# bib.net
KiCad netlist of a schematic drawn in EAGLE
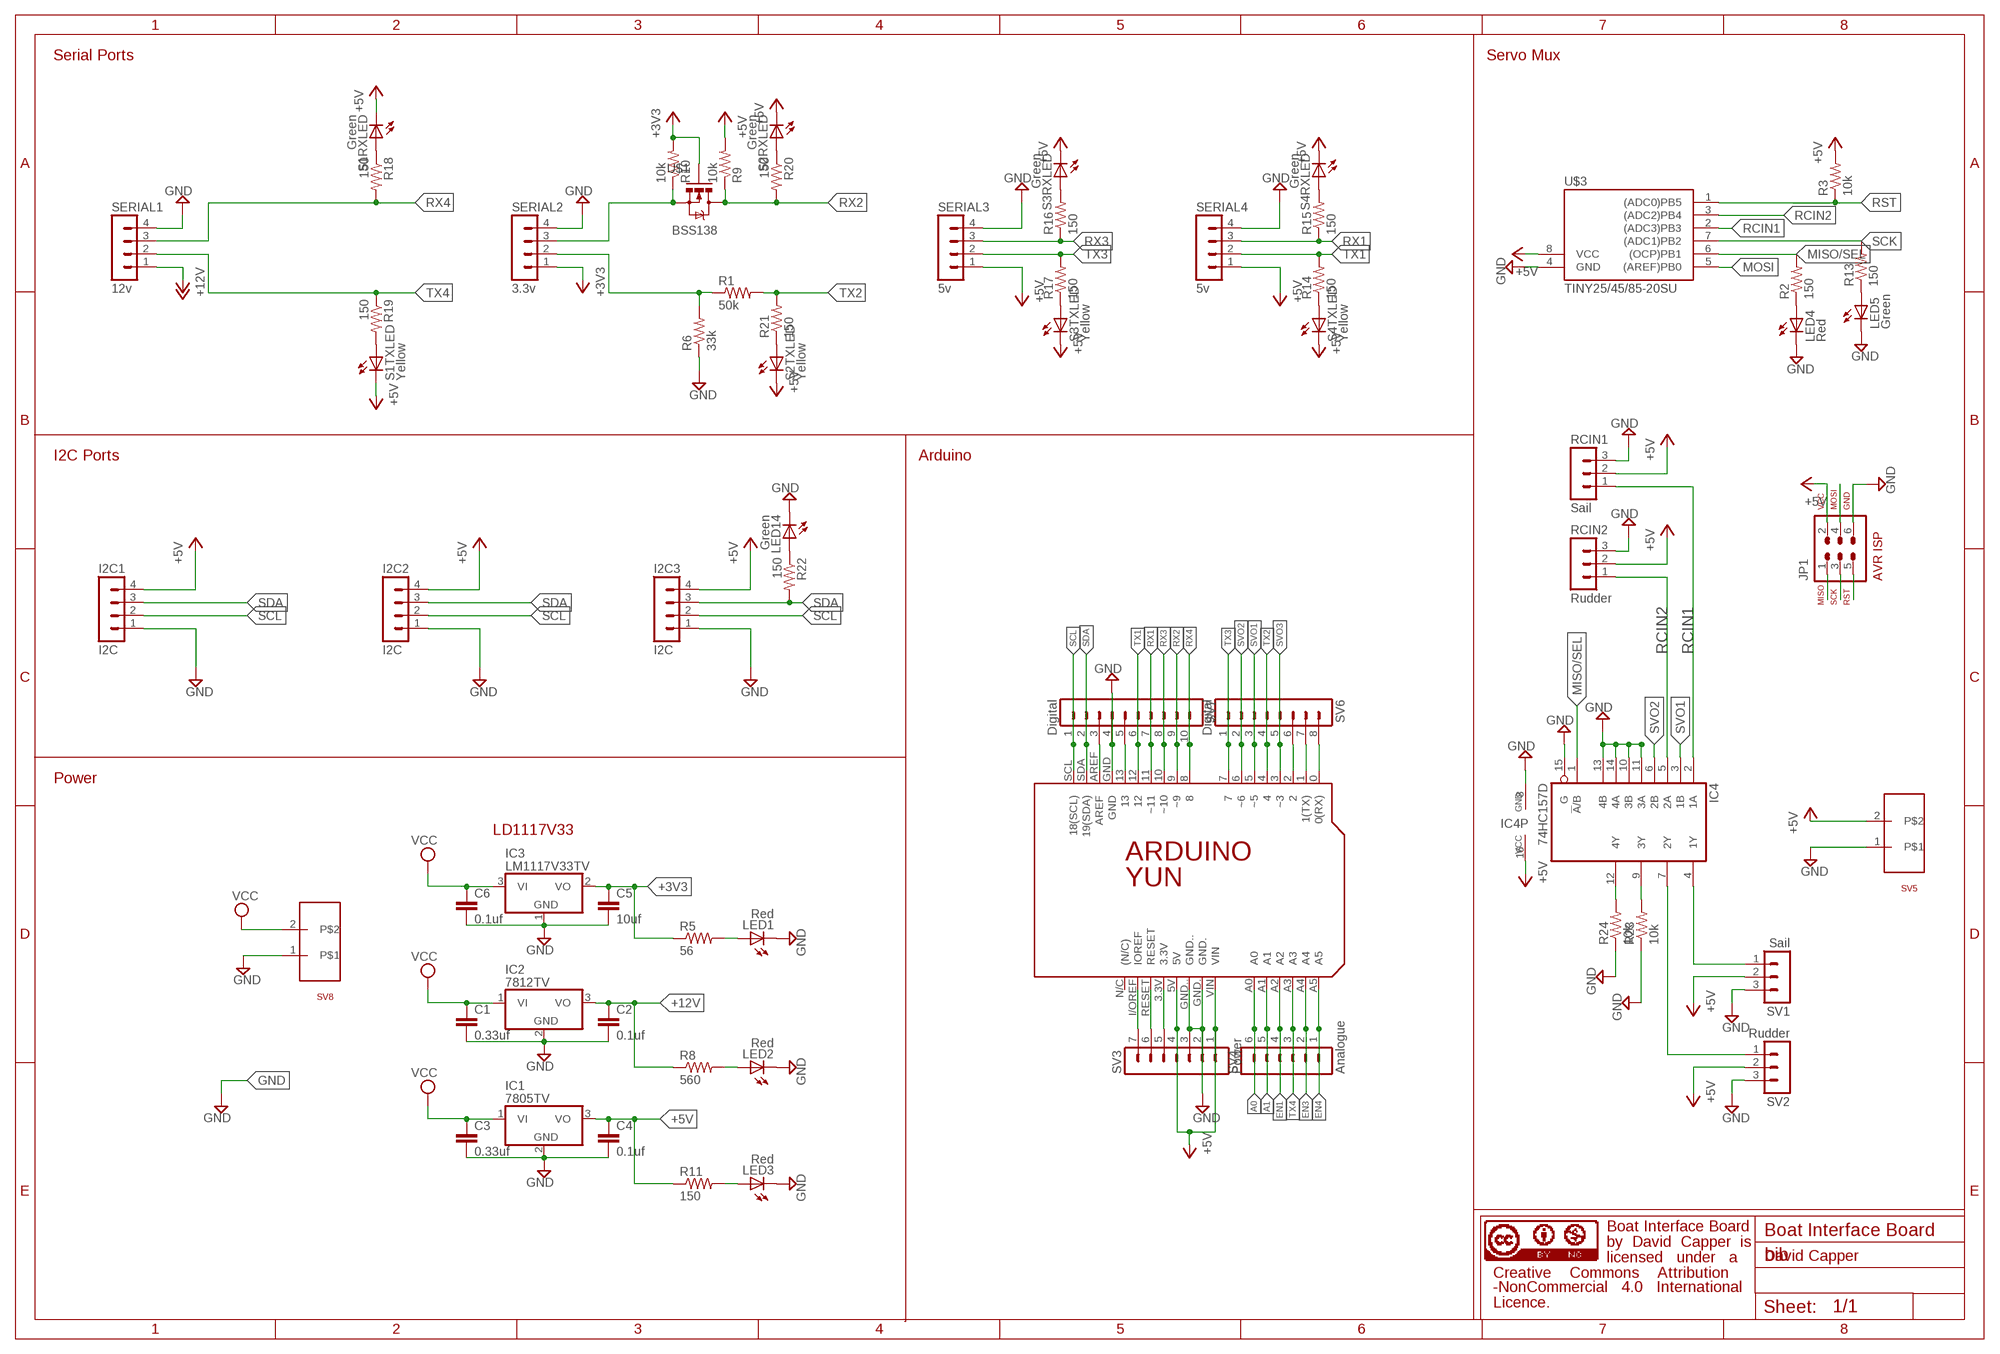
[diagram p0: schematic, sheet 1]

(export (version "E")
  (design (tool "Eeschema 10.0.6"))
  (components
    (comp (ref "C1")
      (value "0.33uf")
      (footprint "eagle-import:C0805K")
      (fields (field (name "MF") "AVX") (field (name "MPN") "08053C334KAT2A"))
      (libsource (lib "eagle-import") (part "C-EUC0805K"))
    )
    (comp (ref "C2")
      (value "0.1uf")
      (footprint "eagle-import:C0805K")
      (fields (field (name "MF") "AVX") (field (name "MPN") "08051C104JAT2A"))
      (libsource (lib "eagle-import") (part "C-EUC0805K"))
    )
    (comp (ref "C3")
      (value "0.33uf")
      (footprint "eagle-import:C0805K")
      (fields (field (name "MF") "AVX") (field (name "MPN") "08053C334KAT2A"))
      (libsource (lib "eagle-import") (part "C-EUC0805K"))
    )
    (comp (ref "C4")
      (value "0.1uf")
      (footprint "eagle-import:C0805K")
      (fields (field (name "MF") "AVX") (field (name "MPN") "08051C104JAT2A"))
      (libsource (lib "eagle-import") (part "C-EUC0805K"))
    )
    (comp (ref "C5")
      (value "10uf")
      (footprint "eagle-import:C0805K")
      (fields (field (name "MF") "YAGEO (PHYCOMP)") (field (name "MPN") "CC0805KRX7R8BB333"))
      (libsource (lib "eagle-import") (part "C-EUC0805K"))
    )
    (comp (ref "C6")
      (value "0.1uf")
      (footprint "eagle-import:C0805K")
      (fields (field (name "MF") "AVX") (field (name "MPN") "08051C104JAT2A"))
      (libsource (lib "eagle-import") (part "C-EUC0805K"))
    )
    (comp (ref "I2C1")
      (value "I2C")
      (footprint "eagle-import:MA04-1")
      (libsource (lib "eagle-import") (part "MA04-1"))
    )
    (comp (ref "I2C2")
      (value "I2C")
      (footprint "eagle-import:MA04-1")
      (libsource (lib "eagle-import") (part "MA04-1"))
    )
    (comp (ref "I2C3")
      (value "I2C")
      (footprint "eagle-import:MA04-1")
      (libsource (lib "eagle-import") (part "MA04-1"))
    )
    (comp (ref "IC1")
      (value "7805TV")
      (footprint "eagle-import:TO220V")
      (fields (field (name "MF") "STMICROELECTRONICS") (field (name "MPN") "L7805ACV"))
      (libsource (lib "eagle-import") (part "78TV05"))
    )
    (comp (ref "IC2")
      (value "7812TV")
      (footprint "eagle-import:TO220V")
      (fields (field (name "MF") "STMICROELECTRONICS") (field (name "MPN") "L7812ACV"))
      (libsource (lib "eagle-import") (part "78TV12"))
    )
    (comp (ref "IC3")
      (value "LM1117V33TV")
      (footprint "eagle-import:TO220V")
      (fields (field (name "MF") "STMICROELECTRONICS") (field (name "MPN") "LD1117V33"))
      (libsource (lib "eagle-import") (part "LM1117V33TV"))
    )
    (comp (ref "IC4")
      (value "74HC157D")
      (footprint "eagle-import:SO16")
      (fields
        (field (name "MF") "TEXAS INSTRUMENTS")
        (field (name "MPN") "SN74HC157D")
        (field (name "OC_FARNELL") "9591150")
      )
      (libsource (lib "eagle-import") (part "74157DHC"))
    )
    (comp (ref "JP1")
      (value "AVR-ISP-6VERT")
      (footprint "eagle-import:AVR-ISP-6")
      (libsource (lib "eagle-import") (part "AVR-ISP-6VERT"))
    )
    (comp (ref "LED1")
      (value "Red")
      (footprint "eagle-import:SML1206")
      (fields (field (name "MF") "KINGBRIGHT") (field (name "MPN") "KPT-3216SRC-J4"))
      (libsource (lib "eagle-import") (part "LEDSML1206"))
    )
    (comp (ref "LED2")
      (value "Red")
      (footprint "eagle-import:SML1206")
      (fields (field (name "MF") "KINGBRIGHT") (field (name "MPN") "KPT-3216SRC-J4"))
      (libsource (lib "eagle-import") (part "LEDSML1206"))
    )
    (comp (ref "LED3")
      (value "Red")
      (footprint "eagle-import:SML1206")
      (fields (field (name "MF") "KINGBRIGHT") (field (name "MPN") "KPT-3216SRC-J4"))
      (libsource (lib "eagle-import") (part "LEDSML1206"))
    )
    (comp (ref "LED4")
      (value "Red")
      (footprint "eagle-import:SML1206")
      (fields (field (name "MF") "KINGBRIGHT") (field (name "MPN") "KPT-3216SGC"))
      (libsource (lib "eagle-import") (part "LEDSML1206"))
    )
    (comp (ref "LED5")
      (value "Green")
      (footprint "eagle-import:SML1206")
      (fields (field (name "MF") "KINGBRIGHT") (field (name "MPN") "KPT-3216SGC"))
      (libsource (lib "eagle-import") (part "LEDSML1206"))
    )
    (comp (ref "LED14")
      (value "Green")
      (footprint "eagle-import:SML1206")
      (fields (field (name "MF") "KINGBRIGHT") (field (name "MPN") "KPT-3216SGC"))
      (libsource (lib "eagle-import") (part "LEDSML1206"))
    )
    (comp (ref "PCB2")
      (value "ARDUINO_YUNARDUINO_YUN")
      (footprint "eagle-import:ARDUINO_YUN")
      (libsource (lib "eagle-import") (part "ARDUINO_YUNARDUINO_YUN"))
    )
    (comp (ref "R1")
      (value "50k")
      (footprint "eagle-import:M0805")
      (fields (field (name "MF") "VISHAY DRALORIC") (field (name "MPN") "CRCW080533K0FKEA"))
      (libsource (lib "eagle-import") (part "R-US_M0805"))
    )
    (comp (ref "R2")
      (value "150")
      (footprint "eagle-import:R0805")
      (fields (field (name "MF") "VISHAY DRALORIC") (field (name "MPN") "CRCW0805150RFKEAHP"))
      (libsource (lib "eagle-import") (part "R-US_R0805"))
    )
    (comp (ref "R3")
      (value "10k")
      (footprint "eagle-import:R0805")
      (fields (field (name "MF") "VISHAY DRALORIC") (field (name "MPN") "CRCW0805150RFKEAHP"))
      (libsource (lib "eagle-import") (part "R-US_R0805"))
    )
    (comp (ref "R5")
      (value "56")
      (footprint "eagle-import:R0805")
      (fields (field (name "MF") "VISHAY DRALORIC") (field (name "MPN") "CRCW080556R0FKEAHP"))
      (libsource (lib "eagle-import") (part "R-US_R0805"))
    )
    (comp (ref "R6")
      (value "33k")
      (footprint "eagle-import:M0805")
      (fields (field (name "MF") "VISHAY DRALORIC") (field (name "MPN") "CRCW080549K9FKEA"))
      (libsource (lib "eagle-import") (part "R-US_M0805"))
    )
    (comp (ref "R8")
      (value "560")
      (footprint "eagle-import:R0805")
      (fields (field (name "MF") "VISHAY DRALORIC") (field (name "MPN") "CRCW0805560RFKEAHP"))
      (libsource (lib "eagle-import") (part "R-US_R0805"))
    )
    (comp (ref "R9")
      (value "10k")
      (footprint "eagle-import:M0805")
      (fields (field (name "MF") "VISHAY DRALORIC") (field (name "MPN") "CRCW080510K0FKEA"))
      (libsource (lib "eagle-import") (part "R-US_M0805"))
    )
    (comp (ref "R10")
      (value "10k")
      (footprint "eagle-import:M0805")
      (fields (field (name "MF") "VISHAY DRALORIC") (field (name "MPN") "CRCW080510K0FKEA"))
      (libsource (lib "eagle-import") (part "R-US_M0805"))
    )
    (comp (ref "R11")
      (value "150")
      (footprint "eagle-import:R0805")
      (fields (field (name "MF") "VISHAY DRALORIC") (field (name "MPN") "CRCW0805150RFKEAHP"))
      (libsource (lib "eagle-import") (part "R-US_R0805"))
    )
    (comp (ref "R13")
      (value "150")
      (footprint "eagle-import:R0805")
      (fields (field (name "MF") "VISHAY DRALORIC") (field (name "MPN") "CRCW0805150RFKEAHP"))
      (libsource (lib "eagle-import") (part "R-US_R0805"))
    )
    (comp (ref "R14")
      (value "150")
      (footprint "eagle-import:R0805")
      (fields (field (name "MF") "VISHAY DRALORIC") (field (name "MPN") "CRCW0805150RFKEAHP"))
      (libsource (lib "eagle-import") (part "R-US_R0805"))
    )
    (comp (ref "R15")
      (value "150")
      (footprint "eagle-import:R0805")
      (fields (field (name "MF") "VISHAY DRALORIC") (field (name "MPN") "CRCW0805150RFKEAHP"))
      (libsource (lib "eagle-import") (part "R-US_R0805"))
    )
    (comp (ref "R16")
      (value "150")
      (footprint "eagle-import:R0805")
      (fields (field (name "MF") "VISHAY DRALORIC") (field (name "MPN") "CRCW0805150RFKEAHP"))
      (libsource (lib "eagle-import") (part "R-US_R0805"))
    )
    (comp (ref "R17")
      (value "150")
      (footprint "eagle-import:R0805")
      (fields (field (name "MF") "VISHAY DRALORIC") (field (name "MPN") "CRCW0805150RFKEAHP"))
      (libsource (lib "eagle-import") (part "R-US_R0805"))
    )
    (comp (ref "R18")
      (value "150")
      (footprint "eagle-import:R0805")
      (fields (field (name "MF") "VISHAY DRALORIC") (field (name "MPN") "CRCW0805150RFKEAHP"))
      (libsource (lib "eagle-import") (part "R-US_R0805"))
    )
    (comp (ref "R19")
      (value "150")
      (footprint "eagle-import:R0805")
      (fields (field (name "MF") "VISHAY DRALORIC") (field (name "MPN") "CRCW0805150RFKEAHP"))
      (libsource (lib "eagle-import") (part "R-US_R0805"))
    )
    (comp (ref "R20")
      (value "150")
      (footprint "eagle-import:R0805")
      (fields (field (name "MF") "VISHAY DRALORIC") (field (name "MPN") "CRCW0805150RFKEAHP"))
      (libsource (lib "eagle-import") (part "R-US_R0805"))
    )
    (comp (ref "R21")
      (value "150")
      (footprint "eagle-import:R0805")
      (fields (field (name "MF") "VISHAY DRALORIC") (field (name "MPN") "CRCW0805150RFKEAHP"))
      (libsource (lib "eagle-import") (part "R-US_R0805"))
    )
    (comp (ref "R22")
      (value "150")
      (footprint "eagle-import:R0805")
      (fields (field (name "MF") "VISHAY DRALORIC") (field (name "MPN") "CRCW0805150RFKEAHP"))
      (libsource (lib "eagle-import") (part "R-US_R0805"))
    )
    (comp (ref "R23")
      (value "10k")
      (footprint "eagle-import:R0805")
      (fields (field (name "MF") "VISHAY DRALORIC") (field (name "MPN") "CRCW080510K0FKEA"))
      (libsource (lib "eagle-import") (part "R-US_R0805"))
    )
    (comp (ref "R24")
      (value "10k")
      (footprint "eagle-import:R0805")
      (fields (field (name "MF") "VISHAY DRALORIC") (field (name "MPN") "CRCW080510K0FKEA"))
      (libsource (lib "eagle-import") (part "R-US_R0805"))
    )
    (comp (ref "RCIN1")
      (value "Sail")
      (footprint "eagle-import:MA03-1")
      (libsource (lib "eagle-import") (part "MA03-1"))
    )
    (comp (ref "RCIN2")
      (value "Rudder")
      (footprint "eagle-import:MA03-1")
      (libsource (lib "eagle-import") (part "MA03-1"))
    )
    (comp (ref "S1RXLED")
      (value "Green")
      (footprint "eagle-import:SML1206")
      (fields (field (name "MF") "KINGBRIGHT") (field (name "MPN") "KPT-3216SGC"))
      (libsource (lib "eagle-import") (part "LEDSML1206"))
    )
    (comp (ref "S1TXLED")
      (value "Yellow")
      (footprint "eagle-import:SML1206")
      (fields (field (name "MF") "KINGBRIGHT") (field (name "MPN") "KPT-3216SYCK"))
      (libsource (lib "eagle-import") (part "LEDSML1206"))
    )
    (comp (ref "S2RXLED")
      (value "Green")
      (footprint "eagle-import:SML1206")
      (fields (field (name "MF") "KINGBRIGHT") (field (name "MPN") "KPT-3216SGC"))
      (libsource (lib "eagle-import") (part "LEDSML1206"))
    )
    (comp (ref "S2TXLED")
      (value "Yellow")
      (footprint "eagle-import:SML1206")
      (fields (field (name "MF") "KINGBRIGHT") (field (name "MPN") "KPT-3216SYCK"))
      (libsource (lib "eagle-import") (part "LEDSML1206"))
    )
    (comp (ref "S3RXLED")
      (value "Green")
      (footprint "eagle-import:SML1206")
      (fields (field (name "MF") "KINGBRIGHT") (field (name "MPN") "KPT-3216SGC"))
      (libsource (lib "eagle-import") (part "LEDSML1206"))
    )
    (comp (ref "S3TXLED")
      (value "Yellow")
      (footprint "eagle-import:SML1206")
      (fields (field (name "MF") "KINGBRIGHT") (field (name "MPN") "KPT-3216SYCK"))
      (libsource (lib "eagle-import") (part "LEDSML1206"))
    )
    (comp (ref "S4RXLED")
      (value "Green")
      (footprint "eagle-import:SML1206")
      (fields (field (name "MF") "KINGBRIGHT") (field (name "MPN") "KPT-3216SGC"))
      (libsource (lib "eagle-import") (part "LEDSML1206"))
    )
    (comp (ref "S4TXLED")
      (value "Yellow")
      (footprint "eagle-import:SML1206")
      (fields (field (name "MF") "KINGBRIGHT") (field (name "MPN") "KPT-3216SYCK"))
      (libsource (lib "eagle-import") (part "LEDSML1206"))
    )
    (comp (ref "SERIAL1")
      (value "12v")
      (footprint "eagle-import:MA04-1")
      (libsource (lib "eagle-import") (part "MA04-1"))
    )
    (comp (ref "SERIAL2")
      (value "3.3v")
      (footprint "eagle-import:MA04-1")
      (libsource (lib "eagle-import") (part "MA04-1"))
    )
    (comp (ref "SERIAL3")
      (value "5v")
      (footprint "eagle-import:MA04-1")
      (libsource (lib "eagle-import") (part "MA04-1"))
    )
    (comp (ref "SERIAL4")
      (value "5v")
      (footprint "eagle-import:MA04-1")
      (libsource (lib "eagle-import") (part "MA04-1"))
    )
    (comp (ref "SV1")
      (value "Sail")
      (footprint "eagle-import:MA03-1")
      (libsource (lib "eagle-import") (part "MA03-1"))
    )
    (comp (ref "SV2")
      (value "Rudder")
      (footprint "eagle-import:MA03-1")
      (libsource (lib "eagle-import") (part "MA03-1"))
    )
    (comp (ref "SV3")
      (value "Power")
      (footprint "eagle-import:MA07-1")
      (libsource (lib "eagle-import") (part "MA07-1"))
    )
    (comp (ref "SV4")
      (value "Analogue")
      (footprint "eagle-import:MA06-1")
      (libsource (lib "eagle-import") (part "MA06-1"))
    )
    (comp (ref "SV5")
      (value "MA02")
      (footprint "eagle-import:MA02-1")
      (libsource (lib "eagle-import") (part "MA02"))
    )
    (comp (ref "SV6")
      (value "Digital")
      (footprint "eagle-import:MA08-1")
      (libsource (lib "eagle-import") (part "MA08-1"))
    )
    (comp (ref "SV7")
      (value "Digital")
      (footprint "eagle-import:MA10-1")
      (libsource (lib "eagle-import") (part "MA10-1"))
    )
    (comp (ref "SV8")
      (value "MA02")
      (footprint "eagle-import:MA02-1")
      (libsource (lib "eagle-import") (part "MA02"))
    )
    (comp (ref "U$1")
      (value "BSS138")
      (footprint "eagle-import:SOT23")
      (fields (field (name "MF") "FAIRCHILD SEMICONDUCTOR"))
      (libsource (lib "eagle-import") (part "BSS138"))
    )
    (comp (ref "U$3")
      (value "TINY25/45/85-20SU")
      (footprint "eagle-import:SOIC8")
      (fields (field (name "MF") "ATMEL") (field (name "MPN") "ATTINY25-20SU"))
      (libsource (lib "eagle-import") (part "TINY25/45/85-20SU"))
    )
  )
  (nets
    (net (code "1") (name "+3V3") (class "Default")
      (node (ref "C5") (pin "1") (pinfunction "1_1") (pintype "passive"))
      (node (ref "IC3") (pin "2") (pinfunction "VO_2") (pintype "passive"))
      (node (ref "R10") (pin "2") (pinfunction "2_2") (pintype "passive"))
      (node (ref "R5") (pin "1") (pinfunction "1_1") (pintype "passive"))
      (node (ref "SERIAL2") (pin "1") (pinfunction "1_1") (pintype "passive"))
      (node (ref "U$1") (pin "1") (pinfunction "G_1") (pintype "passive"))
    )
    (net (code "2") (name "+5V") (class "Default")
      (node (ref "C4") (pin "1") (pinfunction "1_1") (pintype "passive"))
      (node (ref "I2C1") (pin "4") (pinfunction "4_4") (pintype "passive"))
      (node (ref "I2C2") (pin "4") (pinfunction "4_4") (pintype "passive"))
      (node (ref "I2C3") (pin "4") (pinfunction "4_4") (pintype "passive"))
      (node (ref "IC1") (pin "3") (pinfunction "VO_3") (pintype "passive"))
      (node (ref "IC4") (pin "16") (pinfunction "VCC_16") (pintype "power_in"))
      (node (ref "JP1") (pin "2") (pinfunction "2_2") (pintype "passive"))
      (node (ref "PCB2") (pin "5V") (pinfunction "5V_5V") (pintype "bidirectional"))
      (node (ref "PCB2") (pin "VIN") (pinfunction "VIN_VIN") (pintype "bidirectional"))
      (node (ref "R11") (pin "1") (pinfunction "1_1") (pintype "passive"))
      (node (ref "R3") (pin "2") (pinfunction "2_2") (pintype "passive"))
      (node (ref "R9") (pin "2") (pinfunction "2_2") (pintype "passive"))
      (node (ref "RCIN1") (pin "2") (pinfunction "2_2") (pintype "passive"))
      (node (ref "RCIN2") (pin "2") (pinfunction "2_2") (pintype "passive"))
      (node (ref "S1RXLED") (pin "C") (pinfunction "C_C") (pintype "passive"))
      (node (ref "S1TXLED") (pin "C") (pinfunction "C_C") (pintype "passive"))
      (node (ref "S2RXLED") (pin "C") (pinfunction "C_C") (pintype "passive"))
      (node (ref "S2TXLED") (pin "C") (pinfunction "C_C") (pintype "passive"))
      (node (ref "S3RXLED") (pin "C") (pinfunction "C_C") (pintype "passive"))
      (node (ref "S3TXLED") (pin "C") (pinfunction "C_C") (pintype "passive"))
      (node (ref "S4RXLED") (pin "C") (pinfunction "C_C") (pintype "passive"))
      (node (ref "S4TXLED") (pin "C") (pinfunction "C_C") (pintype "passive"))
      (node (ref "SERIAL3") (pin "1") (pinfunction "1_1") (pintype "passive"))
      (node (ref "SERIAL4") (pin "1") (pinfunction "1_1") (pintype "passive"))
      (node (ref "SV1") (pin "2") (pinfunction "2_2") (pintype "passive"))
      (node (ref "SV2") (pin "2") (pinfunction "2_2") (pintype "passive"))
      (node (ref "SV3") (pin "1") (pinfunction "1_1") (pintype "passive"))
      (node (ref "SV3") (pin "4") (pinfunction "4_4") (pintype "passive"))
      (node (ref "SV5") (pin "2") (pinfunction "P$2_2") (pintype "power_in"))
      (node (ref "U$3") (pin "8") (pinfunction "VCC_8") (pintype "power_in"))
    )
    (net (code "3") (name "+12V") (class "Default")
      (node (ref "C2") (pin "1") (pinfunction "1_1") (pintype "passive"))
      (node (ref "IC2") (pin "3") (pinfunction "VO_3") (pintype "passive"))
      (node (ref "R8") (pin "1") (pinfunction "1_1") (pintype "passive"))
      (node (ref "SERIAL1") (pin "1") (pinfunction "1_1") (pintype "passive"))
    )
    (net (code "4") (name "A0") (class "Default")
      (node (ref "PCB2") (pin "A0") (pinfunction "A0_A0") (pintype "bidirectional"))
      (node (ref "SV4") (pin "6") (pinfunction "6_6") (pintype "passive"))
    )
    (net (code "5") (name "A1") (class "Default")
      (node (ref "PCB2") (pin "A1") (pinfunction "A1_A1") (pintype "bidirectional"))
      (node (ref "SV4") (pin "5") (pinfunction "5_5") (pintype "passive"))
    )
    (net (code "6") (name "EN1") (class "Default")
      (node (ref "PCB2") (pin "A2") (pinfunction "A2_A2") (pintype "bidirectional"))
      (node (ref "SV4") (pin "4") (pinfunction "4_4") (pintype "passive"))
    )
    (net (code "7") (name "EN3") (class "Default")
      (node (ref "PCB2") (pin "A4") (pinfunction "A4_A4") (pintype "bidirectional"))
      (node (ref "SV4") (pin "2") (pinfunction "2_2") (pintype "passive"))
    )
    (net (code "8") (name "EN4") (class "Default")
      (node (ref "PCB2") (pin "A5") (pinfunction "A5_A5") (pintype "bidirectional"))
      (node (ref "SV4") (pin "1") (pinfunction "1_1") (pintype "passive"))
    )
    (net (code "9") (name "GND") (class "Default")
      (node (ref "C1") (pin "2") (pinfunction "2_2") (pintype "passive"))
      (node (ref "C2") (pin "2") (pinfunction "2_2") (pintype "passive"))
      (node (ref "C3") (pin "2") (pinfunction "2_2") (pintype "passive"))
      (node (ref "C4") (pin "2") (pinfunction "2_2") (pintype "passive"))
      (node (ref "C5") (pin "2") (pinfunction "2_2") (pintype "passive"))
      (node (ref "C6") (pin "2") (pinfunction "2_2") (pintype "passive"))
      (node (ref "I2C1") (pin "1") (pinfunction "1_1") (pintype "passive"))
      (node (ref "I2C2") (pin "1") (pinfunction "1_1") (pintype "passive"))
      (node (ref "I2C3") (pin "1") (pinfunction "1_1") (pintype "passive"))
      (node (ref "IC1") (pin "2") (pinfunction "GND_2") (pintype "passive"))
      (node (ref "IC2") (pin "2") (pinfunction "GND_2") (pintype "passive"))
      (node (ref "IC3") (pin "1") (pinfunction "GND_1") (pintype "passive"))
      (node (ref "IC4") (pin "10") (pinfunction "3B_10") (pintype "input"))
      (node (ref "IC4") (pin "11") (pinfunction "3A_11") (pintype "input"))
      (node (ref "IC4") (pin "13") (pinfunction "4B_13") (pintype "input"))
      (node (ref "IC4") (pin "14") (pinfunction "4A_14") (pintype "input"))
      (node (ref "IC4") (pin "15") (pinfunction "G_15") (pintype "input"))
      (node (ref "IC4") (pin "8") (pinfunction "GND_8") (pintype "power_in"))
      (node (ref "JP1") (pin "6") (pinfunction "6_6") (pintype "passive"))
      (node (ref "LED1") (pin "C") (pinfunction "C_C") (pintype "passive"))
      (node (ref "LED14") (pin "C") (pinfunction "C_C") (pintype "passive"))
      (node (ref "LED2") (pin "C") (pinfunction "C_C") (pintype "passive"))
      (node (ref "LED3") (pin "C") (pinfunction "C_C") (pintype "passive"))
      (node (ref "LED4") (pin "C") (pinfunction "C_C") (pintype "passive"))
      (node (ref "LED5") (pin "C") (pinfunction "C_C") (pintype "passive"))
      (node (ref "PCB2") (pin "GND") (pinfunction "GND_GND") (pintype "bidirectional"))
      (node (ref "PCB2") (pin "GND.") (pinfunction "GND._GND.") (pintype "bidirectional"))
      (node (ref "PCB2") (pin "GND..") (pinfunction "GND.._GND..") (pintype "bidirectional"))
      (node (ref "R23") (pin "1") (pinfunction "1_1") (pintype "passive"))
      (node (ref "R24") (pin "1") (pinfunction "1_1") (pintype "passive"))
      (node (ref "R6") (pin "1") (pinfunction "1_1") (pintype "passive"))
      (node (ref "RCIN1") (pin "3") (pinfunction "3_3") (pintype "passive"))
      (node (ref "RCIN2") (pin "3") (pinfunction "3_3") (pintype "passive"))
      (node (ref "SERIAL1") (pin "4") (pinfunction "4_4") (pintype "passive"))
      (node (ref "SERIAL2") (pin "4") (pinfunction "4_4") (pintype "passive"))
      (node (ref "SERIAL3") (pin "4") (pinfunction "4_4") (pintype "passive"))
      (node (ref "SERIAL4") (pin "4") (pinfunction "4_4") (pintype "passive"))
      (node (ref "SV1") (pin "3") (pinfunction "3_3") (pintype "passive"))
      (node (ref "SV2") (pin "3") (pinfunction "3_3") (pintype "passive"))
      (node (ref "SV3") (pin "2") (pinfunction "2_2") (pintype "passive"))
      (node (ref "SV3") (pin "3") (pinfunction "3_3") (pintype "passive"))
      (node (ref "SV5") (pin "1") (pinfunction "P$1_1") (pintype "power_in"))
      (node (ref "SV7") (pin "4") (pinfunction "4_4") (pintype "passive"))
      (node (ref "SV8") (pin "1") (pinfunction "P$1_1") (pintype "power_in"))
      (node (ref "U$3") (pin "4") (pinfunction "GND_4") (pintype "power_in"))
    )
    (net (code "10") (name "MISO{slash}SEL") (class "Default")
      (node (ref "IC4") (pin "1") (pinfunction "~{A}/B_1") (pintype "input"))
      (node (ref "JP1") (pin "1") (pinfunction "1_1") (pintype "passive"))
      (node (ref "R2") (pin "2") (pinfunction "2_2") (pintype "passive"))
      (node (ref "U$3") (pin "6") (pinfunction "(OCP)PB1_6") (pintype "bidirectional"))
    )
    (net (code "11") (name "MOSI") (class "Default")
      (node (ref "JP1") (pin "4") (pinfunction "4_4") (pintype "passive"))
      (node (ref "U$3") (pin "5") (pinfunction "(AREF)PB0_5") (pintype "bidirectional"))
    )
    (net (code "12") (name "Net-(IC4A-1Y)") (class "Default")
      (node (ref "IC4") (pin "4") (pinfunction "1Y_4") (pintype "output"))
      (node (ref "SV1") (pin "1") (pinfunction "1_1") (pintype "passive"))
    )
    (net (code "13") (name "Net-(IC4A-2Y)") (class "Default")
      (node (ref "IC4") (pin "7") (pinfunction "2Y_7") (pintype "output"))
      (node (ref "SV2") (pin "1") (pinfunction "1_1") (pintype "passive"))
    )
    (net (code "14") (name "Net-(IC4A-3Y)") (class "Default")
      (node (ref "IC4") (pin "9") (pinfunction "3Y_9") (pintype "output"))
      (node (ref "R23") (pin "2") (pinfunction "2_2") (pintype "passive"))
    )
    (net (code "15") (name "Net-(IC4A-4Y)") (class "Default")
      (node (ref "IC4") (pin "12") (pinfunction "4Y_12") (pintype "output"))
      (node (ref "R24") (pin "2") (pinfunction "2_2") (pintype "passive"))
    )
    (net (code "16") (name "Net-(LED1-PadA)") (class "Default")
      (node (ref "LED1") (pin "A") (pinfunction "A_A") (pintype "passive"))
      (node (ref "R5") (pin "2") (pinfunction "2_2") (pintype "passive"))
    )
    (net (code "17") (name "Net-(LED2-PadA)") (class "Default")
      (node (ref "LED2") (pin "A") (pinfunction "A_A") (pintype "passive"))
      (node (ref "R8") (pin "2") (pinfunction "2_2") (pintype "passive"))
    )
    (net (code "18") (name "Net-(LED3-PadA)") (class "Default")
      (node (ref "LED3") (pin "A") (pinfunction "A_A") (pintype "passive"))
      (node (ref "R11") (pin "2") (pinfunction "2_2") (pintype "passive"))
    )
    (net (code "19") (name "Net-(LED4-PadA)") (class "Default")
      (node (ref "LED4") (pin "A") (pinfunction "A_A") (pintype "passive"))
      (node (ref "R2") (pin "1") (pinfunction "1_1") (pintype "passive"))
    )
    (net (code "20") (name "Net-(LED5-PadA)") (class "Default")
      (node (ref "LED5") (pin "A") (pinfunction "A_A") (pintype "passive"))
      (node (ref "R13") (pin "1") (pinfunction "1_1") (pintype "passive"))
    )
    (net (code "21") (name "Net-(LED14-PadA)") (class "Default")
      (node (ref "LED14") (pin "A") (pinfunction "A_A") (pintype "passive"))
      (node (ref "R22") (pin "1") (pinfunction "1_1") (pintype "passive"))
    )
    (net (code "22") (name "Net-(PCB2-0(RX))") (class "Default")
      (node (ref "PCB2") (pin "0") (pinfunction "0(RX)_0") (pintype "bidirectional"))
      (node (ref "SV6") (pin "8") (pinfunction "8_8") (pintype "passive"))
    )
    (net (code "23") (name "Net-(PCB2-1(TX))") (class "Default")
      (node (ref "PCB2") (pin "1") (pinfunction "1(TX)_1") (pintype "bidirectional"))
      (node (ref "SV6") (pin "7") (pinfunction "7_7") (pintype "passive"))
    )
    (net (code "24") (name "Net-(PCB2-IOREF)") (class "Default")
      (node (ref "PCB2") (pin "I/OREF") (pinfunction "IOREF_I/OREF") (pintype "bidirectional"))
      (node (ref "SV3") (pin "7") (pinfunction "7_7") (pintype "passive"))
    )
    (net (code "25") (name "Net-(PCB2-Pad2)") (class "Default")
      (node (ref "PCB2") (pin "2") (pinfunction "2_2") (pintype "bidirectional"))
      (node (ref "SV6") (pin "6") (pinfunction "6_6") (pintype "passive"))
    )
    (net (code "26") (name "Net-(PCB2-Pad3.3V)") (class "Default")
      (node (ref "PCB2") (pin "3.3V") (pinfunction "3.3V_3.3V") (pintype "bidirectional"))
      (node (ref "SV3") (pin "5") (pinfunction "5_5") (pintype "passive"))
    )
    (net (code "27") (name "Net-(PCB2-Pad13)") (class "Default")
      (node (ref "PCB2") (pin "13") (pinfunction "13_13") (pintype "bidirectional"))
      (node (ref "SV7") (pin "5") (pinfunction "5_5") (pintype "passive"))
    )
    (net (code "28") (name "Net-(PCB2-PadAREF)") (class "Default")
      (node (ref "PCB2") (pin "AREF") (pinfunction "AREF_AREF") (pintype "bidirectional"))
      (node (ref "SV7") (pin "3") (pinfunction "3_3") (pintype "passive"))
    )
    (net (code "29") (name "Net-(PCB2-PadRESET)") (class "Default")
      (node (ref "PCB2") (pin "RESET") (pinfunction "RESET_RESET") (pintype "bidirectional"))
      (node (ref "SV3") (pin "6") (pinfunction "6_6") (pintype "passive"))
    )
    (net (code "30") (name "Net-(R1-Pad1)") (class "Default")
      (node (ref "R1") (pin "1") (pinfunction "1_1") (pintype "passive"))
      (node (ref "R6") (pin "2") (pinfunction "2_2") (pintype "passive"))
      (node (ref "SERIAL2") (pin "2") (pinfunction "2_2") (pintype "passive"))
    )
    (net (code "31") (name "Net-(R14-Pad1)") (class "Default")
      (node (ref "R14") (pin "1") (pinfunction "1_1") (pintype "passive"))
      (node (ref "S4TXLED") (pin "A") (pinfunction "A_A") (pintype "passive"))
    )
    (net (code "32") (name "Net-(R15-Pad2)") (class "Default")
      (node (ref "R15") (pin "2") (pinfunction "2_2") (pintype "passive"))
      (node (ref "S4RXLED") (pin "A") (pinfunction "A_A") (pintype "passive"))
    )
    (net (code "33") (name "Net-(R16-Pad2)") (class "Default")
      (node (ref "R16") (pin "2") (pinfunction "2_2") (pintype "passive"))
      (node (ref "S3RXLED") (pin "A") (pinfunction "A_A") (pintype "passive"))
    )
    (net (code "34") (name "Net-(R17-Pad1)") (class "Default")
      (node (ref "R17") (pin "1") (pinfunction "1_1") (pintype "passive"))
      (node (ref "S3TXLED") (pin "A") (pinfunction "A_A") (pintype "passive"))
    )
    (net (code "35") (name "Net-(R18-Pad1)") (class "Default")
      (node (ref "R18") (pin "1") (pinfunction "1_1") (pintype "passive"))
      (node (ref "S1RXLED") (pin "A") (pinfunction "A_A") (pintype "passive"))
    )
    (net (code "36") (name "Net-(R19-Pad2)") (class "Default")
      (node (ref "R19") (pin "2") (pinfunction "2_2") (pintype "passive"))
      (node (ref "S1TXLED") (pin "A") (pinfunction "A_A") (pintype "passive"))
    )
    (net (code "37") (name "Net-(R20-Pad1)") (class "Default")
      (node (ref "R20") (pin "1") (pinfunction "1_1") (pintype "passive"))
      (node (ref "S2RXLED") (pin "A") (pinfunction "A_A") (pintype "passive"))
    )
    (net (code "38") (name "Net-(R21-Pad1)") (class "Default")
      (node (ref "R21") (pin "1") (pinfunction "1_1") (pintype "passive"))
      (node (ref "S2TXLED") (pin "A") (pinfunction "A_A") (pintype "passive"))
    )
    (net (code "39") (name "Net-(U$1-S)") (class "Default")
      (node (ref "R10") (pin "1") (pinfunction "1_1") (pintype "passive"))
      (node (ref "SERIAL2") (pin "3") (pinfunction "3_3") (pintype "passive"))
      (node (ref "U$1") (pin "2") (pinfunction "S_2") (pintype "passive"))
    )
    (net (code "40") (name "RCIN1") (class "Default")
      (node (ref "IC4") (pin "2") (pinfunction "1A_2") (pintype "input"))
      (node (ref "RCIN1") (pin "1") (pinfunction "1_1") (pintype "passive"))
      (node (ref "U$3") (pin "2") (pinfunction "(ADC3)PB3_2") (pintype "bidirectional"))
    )
    (net (code "41") (name "RCIN2") (class "Default")
      (node (ref "IC4") (pin "5") (pinfunction "2A_5") (pintype "input"))
      (node (ref "RCIN2") (pin "1") (pinfunction "1_1") (pintype "passive"))
      (node (ref "U$3") (pin "3") (pinfunction "(ADC2)PB4_3") (pintype "bidirectional"))
    )
    (net (code "42") (name "RST") (class "Default")
      (node (ref "JP1") (pin "5") (pinfunction "5_5") (pintype "passive"))
      (node (ref "R3") (pin "1") (pinfunction "1_1") (pintype "passive"))
      (node (ref "U$3") (pin "1") (pinfunction "(ADC0)PB5_1") (pintype "bidirectional"))
    )
    (net (code "43") (name "RX1") (class "Default")
      (node (ref "PCB2") (pin "11") (pinfunction "~{11}_11") (pintype "bidirectional"))
      (node (ref "R15") (pin "1") (pinfunction "1_1") (pintype "passive"))
      (node (ref "SERIAL4") (pin "3") (pinfunction "3_3") (pintype "passive"))
      (node (ref "SV7") (pin "7") (pinfunction "7_7") (pintype "passive"))
    )
    (net (code "44") (name "RX2") (class "Default")
      (node (ref "PCB2") (pin "9") (pinfunction "~{9}_9") (pintype "bidirectional"))
      (node (ref "R20") (pin "2") (pinfunction "2_2") (pintype "passive"))
      (node (ref "R9") (pin "1") (pinfunction "1_1") (pintype "passive"))
      (node (ref "SV7") (pin "9") (pinfunction "9_9") (pintype "passive"))
      (node (ref "U$1") (pin "3") (pinfunction "D_3") (pintype "passive"))
    )
    (net (code "45") (name "RX3") (class "Default")
      (node (ref "PCB2") (pin "10") (pinfunction "~{10}_10") (pintype "bidirectional"))
      (node (ref "R16") (pin "1") (pinfunction "1_1") (pintype "passive"))
      (node (ref "SERIAL3") (pin "3") (pinfunction "3_3") (pintype "passive"))
      (node (ref "SV7") (pin "8") (pinfunction "8_8") (pintype "passive"))
    )
    (net (code "46") (name "RX4") (class "Default")
      (node (ref "PCB2") (pin "8") (pinfunction "8_8") (pintype "bidirectional"))
      (node (ref "R18") (pin "2") (pinfunction "2_2") (pintype "passive"))
      (node (ref "SERIAL1") (pin "3") (pinfunction "3_3") (pintype "passive"))
      (node (ref "SV7") (pin "10") (pinfunction "10_10") (pintype "passive"))
    )
    (net (code "47") (name "SCK") (class "Default")
      (node (ref "JP1") (pin "3") (pinfunction "3_3") (pintype "passive"))
      (node (ref "R13") (pin "2") (pinfunction "2_2") (pintype "passive"))
      (node (ref "U$3") (pin "7") (pinfunction "(ADC1)PB2_7") (pintype "bidirectional"))
    )
    (net (code "48") (name "SCL") (class "Default")
      (node (ref "I2C1") (pin "2") (pinfunction "2_2") (pintype "passive"))
      (node (ref "I2C2") (pin "2") (pinfunction "2_2") (pintype "passive"))
      (node (ref "I2C3") (pin "2") (pinfunction "2_2") (pintype "passive"))
      (node (ref "PCB2") (pin "SCL") (pinfunction "18(SCL)_SCL") (pintype "bidirectional"))
      (node (ref "SV7") (pin "1") (pinfunction "1_1") (pintype "passive"))
    )
    (net (code "49") (name "SDA") (class "Default")
      (node (ref "I2C1") (pin "3") (pinfunction "3_3") (pintype "passive"))
      (node (ref "I2C2") (pin "3") (pinfunction "3_3") (pintype "passive"))
      (node (ref "I2C3") (pin "3") (pinfunction "3_3") (pintype "passive"))
      (node (ref "PCB2") (pin "SDA") (pinfunction "19(SDA)_SDA") (pintype "bidirectional"))
      (node (ref "R22") (pin "2") (pinfunction "2_2") (pintype "passive"))
      (node (ref "SV7") (pin "2") (pinfunction "2_2") (pintype "passive"))
    )
    (net (code "50") (name "SVO1") (class "Default")
      (node (ref "IC4") (pin "3") (pinfunction "1B_3") (pintype "input"))
      (node (ref "PCB2") (pin "5") (pinfunction "~{5}_5") (pintype "bidirectional"))
      (node (ref "SV6") (pin "3") (pinfunction "3_3") (pintype "passive"))
    )
    (net (code "51") (name "SVO2") (class "Default")
      (node (ref "IC4") (pin "6") (pinfunction "2B_6") (pintype "input"))
      (node (ref "PCB2") (pin "6") (pinfunction "~{6}_6") (pintype "bidirectional"))
      (node (ref "SV6") (pin "2") (pinfunction "2_2") (pintype "passive"))
    )
    (net (code "52") (name "SVO3") (class "Default")
      (node (ref "PCB2") (pin "3") (pinfunction "~{3}_3") (pintype "bidirectional"))
      (node (ref "SV6") (pin "5") (pinfunction "5_5") (pintype "passive"))
    )
    (net (code "53") (name "TX1") (class "Default")
      (node (ref "PCB2") (pin "12") (pinfunction "12_12") (pintype "bidirectional"))
      (node (ref "R14") (pin "2") (pinfunction "2_2") (pintype "passive"))
      (node (ref "SERIAL4") (pin "2") (pinfunction "2_2") (pintype "passive"))
      (node (ref "SV7") (pin "6") (pinfunction "6_6") (pintype "passive"))
    )
    (net (code "54") (name "TX2") (class "Default")
      (node (ref "PCB2") (pin "4") (pinfunction "4_4") (pintype "bidirectional"))
      (node (ref "R1") (pin "2") (pinfunction "2_2") (pintype "passive"))
      (node (ref "R21") (pin "2") (pinfunction "2_2") (pintype "passive"))
      (node (ref "SV6") (pin "4") (pinfunction "4_4") (pintype "passive"))
    )
    (net (code "55") (name "TX3") (class "Default")
      (node (ref "PCB2") (pin "7") (pinfunction "7_7") (pintype "bidirectional"))
      (node (ref "R17") (pin "2") (pinfunction "2_2") (pintype "passive"))
      (node (ref "SERIAL3") (pin "2") (pinfunction "2_2") (pintype "passive"))
      (node (ref "SV6") (pin "1") (pinfunction "1_1") (pintype "passive"))
    )
    (net (code "56") (name "TX4") (class "Default")
      (node (ref "PCB2") (pin "A3") (pinfunction "A3_A3") (pintype "bidirectional"))
      (node (ref "R19") (pin "1") (pinfunction "1_1") (pintype "passive"))
      (node (ref "SERIAL1") (pin "2") (pinfunction "2_2") (pintype "passive"))
      (node (ref "SV4") (pin "3") (pinfunction "3_3") (pintype "passive"))
    )
    (net (code "57") (name "VCC") (class "Default")
      (node (ref "C1") (pin "1") (pinfunction "1_1") (pintype "passive"))
      (node (ref "C3") (pin "1") (pinfunction "1_1") (pintype "passive"))
      (node (ref "C6") (pin "1") (pinfunction "1_1") (pintype "passive"))
      (node (ref "IC1") (pin "1") (pinfunction "VI_1") (pintype "input"))
      (node (ref "IC2") (pin "1") (pinfunction "VI_1") (pintype "input"))
      (node (ref "IC3") (pin "3") (pinfunction "VI_3") (pintype "input"))
      (node (ref "SV8") (pin "2") (pinfunction "P$2_2") (pintype "power_in"))
    )
    (net (code "58") (name "unconnected-(PCB2-(N{slash}C)-PadN{slash}C)") (class "Default")
      (node (ref "PCB2") (pin "N/C") (pinfunction "(N/C)_N/C") (pintype "bidirectional"))
    )
  )
)
